# sheet5_sensors.net
KiCad netlist of a schematic drawn in Altium Designer
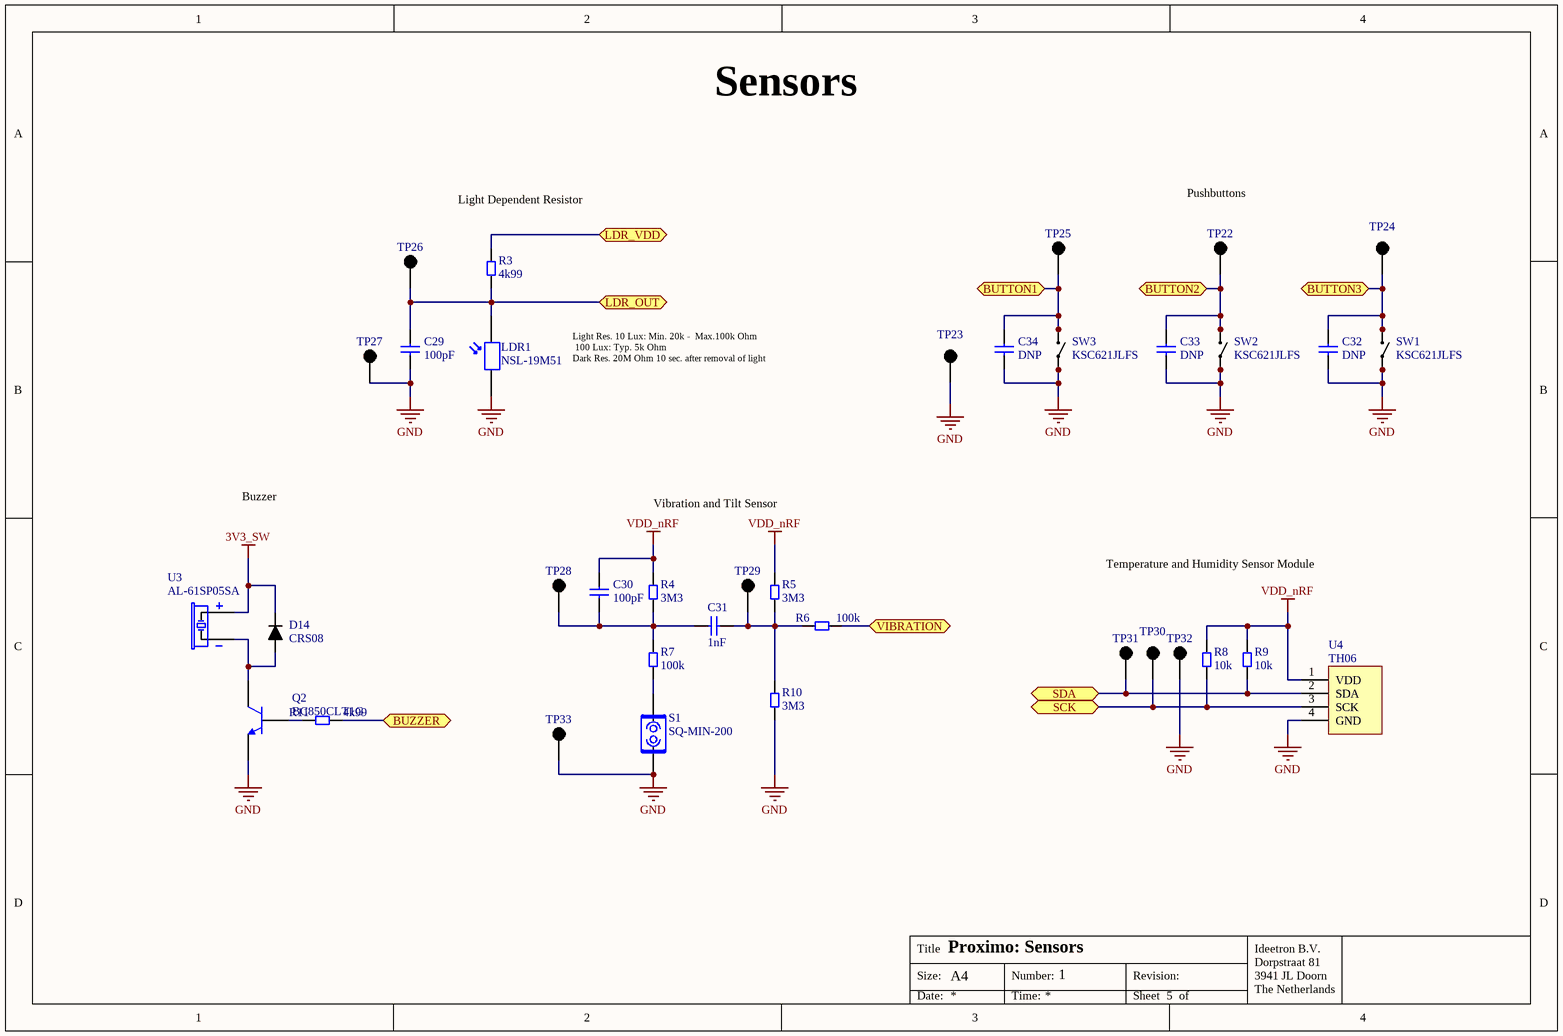
[diagram p0: sheet5_sensors.SchDoc]

(export (version "E")
  (design (tool "Eeschema 10.0.6"))
  (components
    (comp (ref "C29")
      (value "100pF")
      (footprint "CAP0603_GCx18_MURATA")
      (description "Capacitor 100pF 0603 NP0")
      (fields
        (field (name "MANUFACTURER") "Murata")
        (field (name "MANUFACTURER PART NUMBER") "GCM1885C1H101JA16D")
      )
      (libsource (lib "Schlib") (part "CAP_0603_100pF"))
    )
    (comp (ref "C30")
      (value "100pF")
      (footprint "CAP0603_GCx18_MURATA")
      (description "Capacitor 100pF 0603 NP0")
      (fields
        (field (name "MANUFACTURER") "Murata")
        (field (name "MANUFACTURER PART NUMBER") "GCM1885C1H101JA16D")
      )
      (libsource (lib "Schlib") (part "CAP_0603_100pF"))
    )
    (comp (ref "C31")
      (value "1nF")
      (footprint "CAP0402_GCx18_Murata")
      (description "Capacitor 1nF 0402")
      (fields
        (field (name "MANUFACTURER") "Murata")
        (field (name "MANUFACTURER PART NUMBER") "GCM188R72A102KA37D")
      )
      (libsource (lib "Schlib") (part "CAP_0402_1nF"))
    )
    (comp (ref "C32")
      (value "~")
      (footprint "CAP0603_GCx18_MURATA")
      (description "Capacitor 100pF 0603 NP0")
      (fields (field (name "REMARK") "DNP"))
      (libsource (lib "Schlib") (part "CAP_0603_100pF"))
    )
    (comp (ref "C33")
      (value "~")
      (footprint "CAP0603_GCx18_MURATA")
      (description "Capacitor 100pF 0603 NP0")
      (fields (field (name "REMARK") "DNP"))
      (libsource (lib "Schlib") (part "CAP_0603_100pF"))
    )
    (comp (ref "C34")
      (value "~")
      (footprint "CAP0603_GCx18_MURATA")
      (description "Capacitor 100pF 0603 NP0")
      (fields (field (name "REMARK") "DNP"))
      (libsource (lib "Schlib") (part "CAP_0603_100pF"))
    )
    (comp (ref "D14")
      (value "CRS08")
      (footprint "SOD-123F")
      (description "CRS08 Schottky Diode")
      (fields (field (name "MANUFACTURER") "Tohsiba"))
      (libsource (lib "Schlib") (part "CRS08 Schottky Diode"))
    )
    (comp (ref "LDR1")
      (value "NSL-19M51")
      (footprint "LDR")
      (description "Light Dependant Resistor Phot")
      (fields (field (name "MANUFACTURER") "Luna Optoelectronics"))
      (libsource (lib "Schlib") (part "LDR"))
    )
    (comp (ref "Q2")
      (value "BC850CLT1G")
      (footprint "SOT23")
      (description "NPN general purpose transistor")
      (fields
        (field (name "MANUFACTURER") "On Semiconductor")
        (field (name "MANUFACTURER PART NUMBER") "NSVBC850CLT1G")
      )
      (libsource (lib "Schlib") (part "BC850C"))
    )
    (comp (ref "R3")
      (value "4k99")
      (footprint "RES0603VISHAY")
      (description "SMD Resistor 4k99 0603")
      (fields
        (field (name "MANUFACTURER") "Vishay")
        (field (name "MANUFACTURER PART NUMBER") "CRCW06034K99FKTABC")
      )
      (libsource (lib "Schlib") (part "Resistor_4k99"))
    )
    (comp (ref "R4")
      (value "3M3")
      (footprint "RES0603VISHAY")
      (description "SMD Resistor 3M3 0603")
      (fields
        (field (name "MANUFACTURER") "Vishay")
        (field (name "MANUFACTURER PART NUMBER") "CRCW06033M30FKTABC")
      )
      (libsource (lib "Schlib") (part "Resistor_3M3"))
    )
    (comp (ref "R5")
      (value "3M3")
      (footprint "RES0603VISHAY")
      (description "SMD Resistor 3M3 0603")
      (fields
        (field (name "MANUFACTURER") "Vishay")
        (field (name "MANUFACTURER PART NUMBER") "CRCW06033M30FKTABC")
      )
      (libsource (lib "Schlib") (part "Resistor_3M3"))
    )
    (comp (ref "R6")
      (value "100k")
      (footprint "RES0603VISHAY")
      (description "SMD Resistor 100k 0603")
      (fields
        (field (name "MANUFACTURER") "Vishay")
        (field (name "MANUFACTURER PART NUMBER") "CRCW0603100KFKTABC")
      )
      (libsource (lib "Schlib") (part "Resistor_100k"))
    )
    (comp (ref "R7")
      (value "100k")
      (footprint "RES0603VISHAY")
      (description "SMD Resistor 100k 0603")
      (fields
        (field (name "MANUFACTURER") "Vishay")
        (field (name "MANUFACTURER PART NUMBER") "CRCW0603100KFKTABC")
      )
      (libsource (lib "Schlib") (part "Resistor_100k"))
    )
    (comp (ref "R8")
      (value "10k")
      (footprint "RES0603VISHAY")
      (description "SMD Resistor 10k 0603")
      (fields
        (field (name "MANUFACTURER") "Vishay")
        (field (name "MANUFACTURER PART NUMBER") "CRCW060310K0FKTABC")
      )
      (libsource (lib "Schlib") (part "Resistor_10k"))
    )
    (comp (ref "R9")
      (value "10k")
      (footprint "RES0603VISHAY")
      (description "SMD Resistor 10k 0603")
      (fields
        (field (name "MANUFACTURER") "Vishay")
        (field (name "MANUFACTURER PART NUMBER") "CRCW060310K0FKTABC")
      )
      (libsource (lib "Schlib") (part "Resistor_10k"))
    )
    (comp (ref "R10")
      (value "3M3")
      (footprint "RES0603VISHAY")
      (description "SMD Resistor 3M3 0603")
      (fields
        (field (name "MANUFACTURER") "Vishay")
        (field (name "MANUFACTURER PART NUMBER") "CRCW06033M30FKTABC")
      )
      (libsource (lib "Schlib") (part "Resistor_3M3"))
    )
    (comp (ref "R11")
      (value "4k99")
      (footprint "RES0603VISHAY")
      (description "SMD Resistor 4k99 0603")
      (fields
        (field (name "MANUFACTURER") "Vishay")
        (field (name "MANUFACTURER PART NUMBER") "CRCW06034K99FKTABC")
      )
      (libsource (lib "Schlib") (part "Resistor_4k99"))
    )
    (comp (ref "S1")
      (value "SQ-MIN-200")
      (footprint "SQ-SEN-200")
      (description "Nano Power Tilt and Vibration sensor")
      (fields (field (name "MANUFACTURER") "SignalQuest"))
      (libsource (lib "Schlib") (part "SQ-MIN-200"))
    )
    (comp (ref "SW1")
      (value "KSC621JLFS")
      (footprint "KSC621JLFS")
      (description "Tactile switch SMT")
      (fields (field (name "MANUFACTURER") "C & K Components"))
      (libsource (lib "Schlib") (part "KSC621JLFS Tactile switch SMT"))
    )
    (comp (ref "SW2")
      (value "KSC621JLFS")
      (footprint "KSC621JLFS")
      (description "Tactile switch SMT")
      (fields (field (name "MANUFACTURER") "C & K Components"))
      (libsource (lib "Schlib") (part "KSC621JLFS Tactile switch SMT"))
    )
    (comp (ref "SW3")
      (value "KSC621JLFS")
      (footprint "KSC621JLFS")
      (description "Tactile switch SMT")
      (fields (field (name "MANUFACTURER") "C & K Components"))
      (libsource (lib "Schlib") (part "KSC621JLFS Tactile switch SMT"))
    )
    (comp (ref "TP22")
      (value "testpad")
      (footprint "TestPad")
      (description "Signal probe pad")
      (libsource (lib "Schlib") (part "TestPad"))
    )
    (comp (ref "TP23")
      (value "testpad")
      (footprint "TestPad")
      (description "Signal probe pad")
      (libsource (lib "Schlib") (part "TestPad"))
    )
    (comp (ref "TP24")
      (value "testpad")
      (footprint "TestPad")
      (description "Signal probe pad")
      (libsource (lib "Schlib") (part "TestPad"))
    )
    (comp (ref "TP25")
      (value "testpad")
      (footprint "TestPad")
      (description "Signal probe pad")
      (libsource (lib "Schlib") (part "TestPad"))
    )
    (comp (ref "TP26")
      (value "testpad")
      (footprint "TestPad")
      (description "Signal probe pad")
      (libsource (lib "Schlib") (part "TestPad"))
    )
    (comp (ref "TP27")
      (value "testpad")
      (footprint "TestPad")
      (description "Signal probe pad")
      (libsource (lib "Schlib") (part "TestPad"))
    )
    (comp (ref "TP28")
      (value "testpad")
      (footprint "TestPad")
      (description "Signal probe pad")
      (libsource (lib "Schlib") (part "TestPad"))
    )
    (comp (ref "TP29")
      (value "testpad")
      (footprint "TestPad")
      (description "Signal probe pad")
      (libsource (lib "Schlib") (part "TestPad"))
    )
    (comp (ref "TP30")
      (value "testpad")
      (footprint "TestPad")
      (description "Signal probe pad")
      (libsource (lib "Schlib") (part "TestPad"))
    )
    (comp (ref "TP31")
      (value "testpad")
      (footprint "TestPad")
      (description "Signal probe pad")
      (libsource (lib "Schlib") (part "TestPad"))
    )
    (comp (ref "TP32")
      (value "testpad")
      (footprint "TestPad")
      (description "Signal probe pad")
      (libsource (lib "Schlib") (part "TestPad"))
    )
    (comp (ref "TP33")
      (value "testpad")
      (footprint "TestPad")
      (description "Signal probe pad")
      (libsource (lib "Schlib") (part "TestPad"))
    )
    (comp (ref "U3")
      (value "AL-61SP05SA")
      (footprint "Buzzer - AL-61SP05SA")
      (description "Piezo Buzzer")
      (fields (field (name "MANUFACTURER") "EKULIT"))
      (libsource (lib "Schlib") (part "PiezoBuzzer"))
    )
    (comp (ref "U4")
      (value "TH06")
      (footprint "TH06_module")
      (description "I2C Humidity and Temperature Sensor module")
      (fields (field (name "MANUFACTURER") "HopeRF"))
      (libsource (lib "Schlib") (part "TH06"))
    )
  )
  (nets
    (net (code "1") (name "/BUTTON1") (class "Default")
      (node (ref "C34") (pin "2") (pinfunction "2_2") (pintype "passive"))
      (node (ref "SW3") (pin "1") (pinfunction "1_1") (pintype "passive"))
      (node (ref "SW3") (pin "2") (pinfunction "2_2") (pintype "passive"))
      (node (ref "TP25") (pin "1") (pinfunction "1_1") (pintype "passive"))
    )
    (net (code "2") (name "/BUTTON2") (class "Default")
      (node (ref "C33") (pin "2") (pinfunction "2_2") (pintype "passive"))
      (node (ref "SW2") (pin "1") (pinfunction "1_1") (pintype "passive"))
      (node (ref "SW2") (pin "2") (pinfunction "2_2") (pintype "passive"))
      (node (ref "TP22") (pin "1") (pinfunction "1_1") (pintype "passive"))
    )
    (net (code "3") (name "/BUTTON3") (class "Default")
      (node (ref "C32") (pin "2") (pinfunction "2_2") (pintype "passive"))
      (node (ref "SW1") (pin "1") (pinfunction "1_1") (pintype "passive"))
      (node (ref "SW1") (pin "2") (pinfunction "2_2") (pintype "passive"))
      (node (ref "TP24") (pin "1") (pinfunction "1_1") (pintype "passive"))
    )
    (net (code "4") (name "/BUZZER") (class "Default")
      (node (ref "R11") (pin "2") (pinfunction "2_2") (pintype "passive"))
    )
    (net (code "5") (name "/LDR_OUT") (class "Default")
      (node (ref "C29") (pin "2") (pinfunction "2_2") (pintype "passive"))
      (node (ref "LDR1") (pin "2") (pinfunction "2_2") (pintype "passive"))
      (node (ref "R3") (pin "1") (pinfunction "1_1") (pintype "passive"))
      (node (ref "TP26") (pin "1") (pinfunction "1_1") (pintype "passive"))
    )
    (net (code "6") (name "/LDR_VDD") (class "Default")
      (node (ref "R3") (pin "2") (pinfunction "2_2") (pintype "passive"))
    )
    (net (code "7") (name "/SCK") (class "Default")
      (node (ref "R8") (pin "1") (pinfunction "1_1") (pintype "passive"))
      (node (ref "TP30") (pin "1") (pinfunction "1_1") (pintype "passive"))
      (node (ref "U4") (pin "3") (pinfunction "SCK_3") (pintype "passive"))
    )
    (net (code "8") (name "/SDA") (class "Default")
      (node (ref "R9") (pin "1") (pinfunction "1_1") (pintype "passive"))
      (node (ref "TP31") (pin "1") (pinfunction "1_1") (pintype "passive"))
      (node (ref "U4") (pin "2") (pinfunction "SDA_2") (pintype "passive"))
    )
    (net (code "9") (name "/VIBRATION") (class "Default")
      (node (ref "R6") (pin "1") (pinfunction "1_1") (pintype "passive"))
    )
    (net (code "10") (name "3V3_SW") (class "Default")
      (node (ref "D14") (pin "C") (pinfunction "C_C") (pintype "passive"))
      (node (ref "U3") (pin "2") (pinfunction "2_2") (pintype "passive"))
    )
    (net (code "11") (name "GND") (class "Default")
      (node (ref "C29") (pin "1") (pinfunction "1_1") (pintype "passive"))
      (node (ref "C32") (pin "1") (pinfunction "1_1") (pintype "passive"))
      (node (ref "C33") (pin "1") (pinfunction "1_1") (pintype "passive"))
      (node (ref "C34") (pin "1") (pinfunction "1_1") (pintype "passive"))
      (node (ref "LDR1") (pin "1") (pinfunction "1_1") (pintype "passive"))
      (node (ref "Q2") (pin "2") (pinfunction "2_2") (pintype "passive"))
      (node (ref "R10") (pin "1") (pinfunction "1_1") (pintype "passive"))
      (node (ref "S1") (pin "1") (pinfunction "1_1") (pintype "passive"))
      (node (ref "SW1") (pin "3") (pinfunction "3_3") (pintype "passive"))
      (node (ref "SW1") (pin "4") (pinfunction "4_4") (pintype "passive"))
      (node (ref "SW2") (pin "3") (pinfunction "3_3") (pintype "passive"))
      (node (ref "SW2") (pin "4") (pinfunction "4_4") (pintype "passive"))
      (node (ref "SW3") (pin "3") (pinfunction "3_3") (pintype "passive"))
      (node (ref "SW3") (pin "4") (pinfunction "4_4") (pintype "passive"))
      (node (ref "TP23") (pin "1") (pinfunction "1_1") (pintype "passive"))
      (node (ref "TP27") (pin "1") (pinfunction "1_1") (pintype "passive"))
      (node (ref "TP32") (pin "1") (pinfunction "1_1") (pintype "passive"))
      (node (ref "TP33") (pin "1") (pinfunction "1_1") (pintype "passive"))
      (node (ref "U4") (pin "4") (pinfunction "GND_4") (pintype "passive"))
    )
    (net (code "12") (name "Net-(C30-Pad1)") (class "Default")
      (node (ref "C30") (pin "1") (pinfunction "1_1") (pintype "passive"))
      (node (ref "C31") (pin "1") (pinfunction "1_1") (pintype "passive"))
      (node (ref "R4") (pin "1") (pinfunction "1_1") (pintype "passive"))
      (node (ref "R7") (pin "2") (pinfunction "2_2") (pintype "passive"))
      (node (ref "TP28") (pin "1") (pinfunction "1_1") (pintype "passive"))
    )
    (net (code "13") (name "Net-(C31-Pad2)") (class "Default")
      (node (ref "C31") (pin "2") (pinfunction "2_2") (pintype "passive"))
      (node (ref "R10") (pin "2") (pinfunction "2_2") (pintype "passive"))
      (node (ref "R5") (pin "1") (pinfunction "1_1") (pintype "passive"))
      (node (ref "R6") (pin "2") (pinfunction "2_2") (pintype "passive"))
      (node (ref "TP29") (pin "1") (pinfunction "1_1") (pintype "passive"))
    )
    (net (code "14") (name "Net-(D14-PadA)") (class "Default")
      (node (ref "D14") (pin "A") (pinfunction "A_A") (pintype "passive"))
      (node (ref "Q2") (pin "3") (pinfunction "3_3") (pintype "passive"))
      (node (ref "U3") (pin "1") (pinfunction "1_1") (pintype "passive"))
    )
    (net (code "15") (name "Net-(Q2-Pad1)") (class "Default")
      (node (ref "Q2") (pin "1") (pinfunction "1_1") (pintype "passive"))
      (node (ref "R11") (pin "1") (pinfunction "1_1") (pintype "passive"))
    )
    (net (code "16") (name "Net-(R7-Pad1)") (class "Default")
      (node (ref "R7") (pin "1") (pinfunction "1_1") (pintype "passive"))
      (node (ref "S1") (pin "2") (pinfunction "2_2") (pintype "passive"))
    )
    (net (code "17") (name "VDD_nRF") (class "Default")
      (node (ref "C30") (pin "2") (pinfunction "2_2") (pintype "passive"))
      (node (ref "R4") (pin "2") (pinfunction "2_2") (pintype "passive"))
      (node (ref "R5") (pin "2") (pinfunction "2_2") (pintype "passive"))
      (node (ref "R8") (pin "2") (pinfunction "2_2") (pintype "passive"))
      (node (ref "R9") (pin "2") (pinfunction "2_2") (pintype "passive"))
      (node (ref "U4") (pin "1") (pinfunction "VDD_1") (pintype "passive"))
    )
  )
)
